# Sheet1.net
KiCad netlist of a schematic drawn in Altium Designer
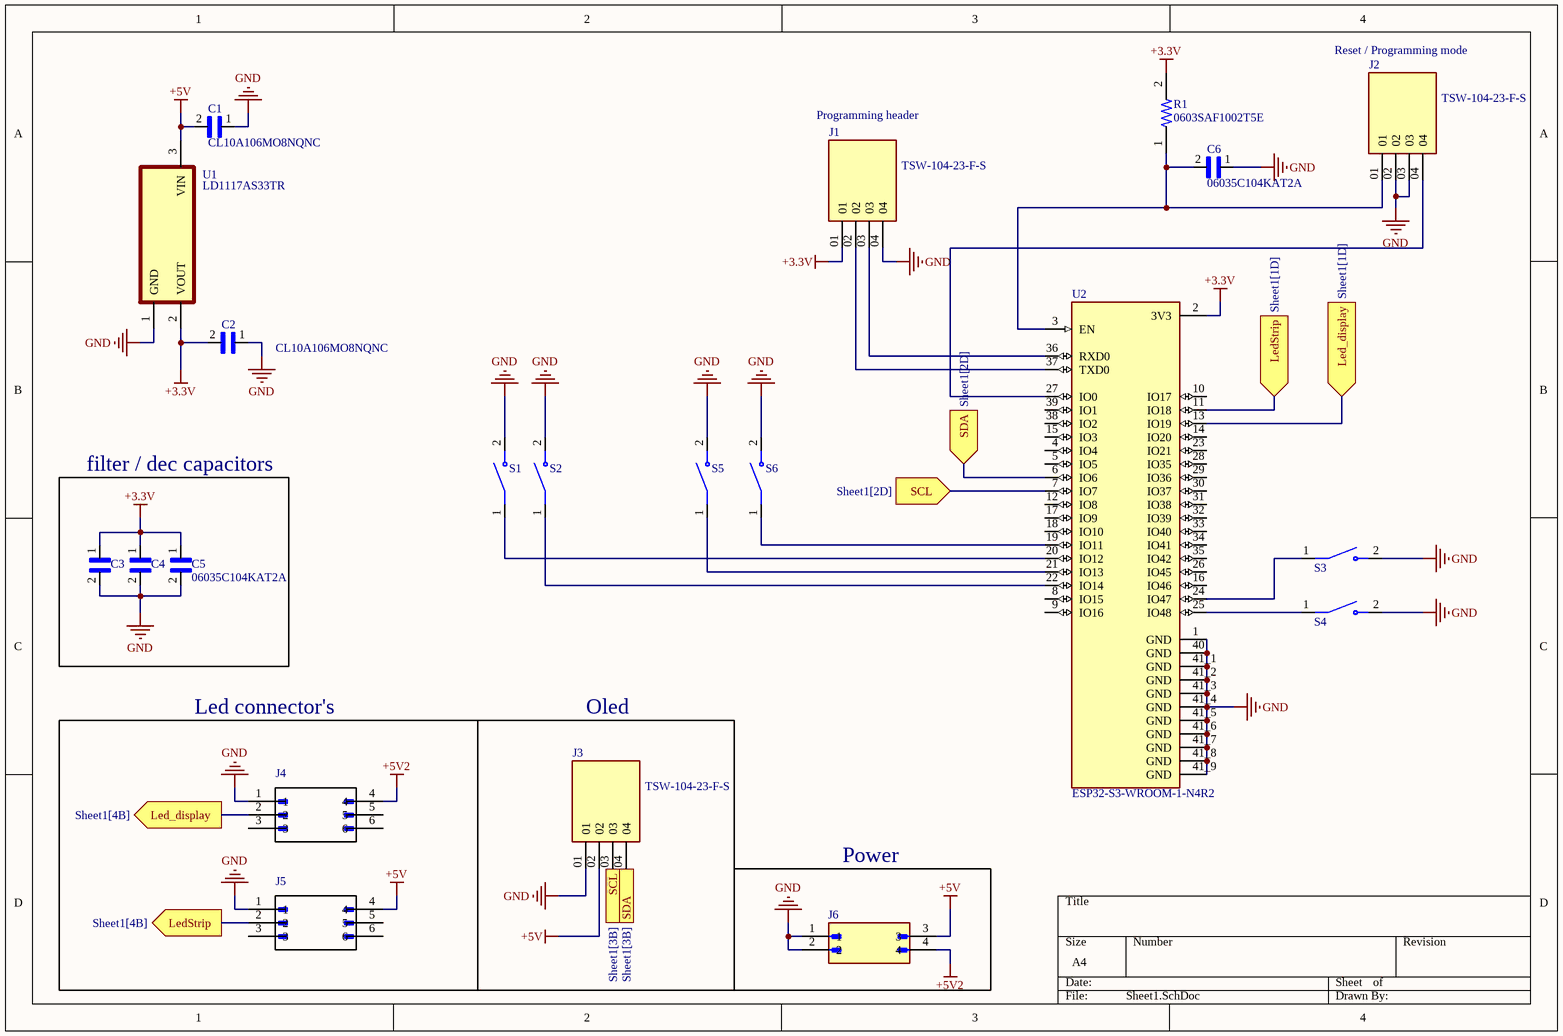
[diagram p0: Sheet1.SchDoc]

(export (version "E")
  (design (tool "Eeschema 10.0.6"))
  (components
    (comp (ref "C1")
      (value "CL10A106MO8NQNC")
      (footprint "CL10A106MO8NQNC:CAPC1608X90N")
      (description "Cap Ceramic 10uF 16V X5R 20% SMD 0603 85Â°C Paper T/R")
      (fields (field (name "MF") "{'manufacturer': u'Samsung Electro-Mechanics'}"))
      (libsource (lib "*") (part "CL10A106MO8NQNC"))
    )
    (comp (ref "C2")
      (value "CL10A106MO8NQNC")
      (footprint "CL10A106MO8NQNC:CAPC1608X90N")
      (description "Cap Ceramic 10uF 16V X5R 20% SMD 0603 85Â°C Paper T/R")
      (fields (field (name "MF") "{'manufacturer': u'Samsung Electro-Mechanics'}"))
      (libsource (lib "*") (part "CL10A106MO8NQNC"))
    )
    (comp (ref "C3")
      (value "06035C104KAT2A")
      (footprint "06035C104KAT2A:CAPC1608X90N")
      (fields (field (name "MF") "{'manufacturer': u'AVX'}"))
      (libsource (lib "") (part "06035C104KAT2A_1"))
    )
    (comp (ref "C4")
      (value "06035C104KAT2A")
      (footprint "06035C104KAT2A:CAPC1608X90N")
      (fields (field (name "MF") "{'manufacturer': u'AVX'}"))
      (libsource (lib "") (part "06035C104KAT2A_1"))
    )
    (comp (ref "C5")
      (value "06035C104KAT2A")
      (footprint "06035C104KAT2A:CAPC1608X90N")
      (fields (field (name "MF") "{'manufacturer': u'AVX'}"))
      (libsource (lib "") (part "06035C104KAT2A_1"))
    )
    (comp (ref "C6")
      (value "06035C104KAT2A")
      (footprint "06035C104KAT2A:CAPC1608X90N")
      (fields (field (name "MF") "{'manufacturer': u'AVX'}"))
      (libsource (lib "*") (part "06035C104KAT2A"))
    )
    (comp (ref "J1")
      (value "TSW-104-23-F-S")
      (footprint "TSW-104-23-F-S:SAMTEC_TSW-104-23-F-S")
      (fields (field (name "MF") "{'manufacturer': u'Samtec'}"))
      (libsource (lib "*") (part "TSW-104-23-F-S"))
    )
    (comp (ref "J2")
      (value "TSW-104-23-F-S")
      (footprint "TSW-104-23-F-S:SAMTEC_TSW-104-23-F-S")
      (fields (field (name "MF") "{'manufacturer': u'Samtec'}"))
      (libsource (lib "*") (part "TSW-104-23-F-S"))
    )
    (comp (ref "J3")
      (value "TSW-104-23-F-S")
      (footprint "TSW-104-23-F-S:SAMTEC_TSW-104-23-F-S")
      (fields (field (name "MF") "{'manufacturer': u'Samtec'}"))
      (libsource (lib "*") (part "TSW-104-23-F-S"))
    )
    (comp (ref "J4")
      (value "874270602")
      (footprint "*MOLEX_874270602")
      (libsource (lib "874270602") (part "874270602"))
    )
    (comp (ref "J5")
      (value "874270602")
      (footprint "*MOLEX_874270602")
      (libsource (lib "874270602") (part "874270602"))
    )
    (comp (ref "J6")
      (value "353180420")
      (footprint "*MOLEX_353180420")
      (description "Connector Header Through Hole, Right Angle 4 position 0.165in (4.20mm)")
      (fields (field (name "MF") "{'manufacturer': u'Molex'}"))
      (libsource (lib "*") (part "353180420"))
    )
    (comp (ref "R1")
      (value "0603SAF1002T5E")
      (footprint "RP73PF1J10KBTDF:RESC1608X50N")
      (description "0603 10k ohm")
      (fields
        (field (name "MF") "{'manufacturer': u'TE Connectivity'}")
        (field (name "MP") "RP73PF1J10KBTDF")
      )
      (libsource (lib "*") (part "RP73PF1J10KBTDF"))
    )
    (comp (ref "S1")
      (value "TL1107BF130WQ")
      (footprint "SW_MX_reversible")
      (fields (field (name "MF") "{'manufacturer': u'E-Switch'}"))
      (libsource (lib "TL1107BF130WQ") (part "TL1107BF130WQ"))
    )
    (comp (ref "S2")
      (value "TL1107BF130WQ")
      (footprint "SW_MX_reversible")
      (fields (field (name "MF") "{'manufacturer': u'E-Switch'}"))
      (libsource (lib "TL1107BF130WQ") (part "TL1107BF130WQ"))
    )
    (comp (ref "S3")
      (value "TL1107BF130WQ")
      (footprint "SW_MX_reversible")
      (fields (field (name "MF") "{'manufacturer': u'E-Switch'}"))
      (libsource (lib "TL1107BF130WQ") (part "TL1107BF130WQ"))
    )
    (comp (ref "S4")
      (value "TL1107BF130WQ")
      (footprint "SW_MX_reversible")
      (fields (field (name "MF") "{'manufacturer': u'E-Switch'}"))
      (libsource (lib "TL1107BF130WQ") (part "TL1107BF130WQ"))
    )
    (comp (ref "S5")
      (value "TL1107BF130WQ")
      (footprint "SW_MX_reversible")
      (fields (field (name "MF") "{'manufacturer': u'E-Switch'}"))
      (libsource (lib "TL1107BF130WQ") (part "TL1107BF130WQ"))
    )
    (comp (ref "S6")
      (value "TL1107BF130WQ")
      (footprint "SW_MX_reversible")
      (fields (field (name "MF") "{'manufacturer': u'E-Switch'}"))
      (libsource (lib "TL1107BF130WQ") (part "TL1107BF130WQ"))
    )
    (comp (ref "U1")
      (value "LD1117AS33TR")
      (footprint "LD1117AS33TR:SOT230P700X180-4N")
      (fields (field (name "MF") "{'manufacturer': u'STMicroelectronics'}"))
      (libsource (lib "*") (part "LD1117AS33TR"))
    )
    (comp (ref "U2")
      (value "ESP32-S3-WROOM-1-N4R2")
      (footprint "XCVR_ESP32-S3-WROOM-1-N4R2")
      (fields (field (name "MF") "{'manufacturer': u'Espressif Systems'}"))
      (libsource (lib "ESP32-S3-WROOM-1-N4R2") (part "ESP32-S3-WROOM-1-N4R2"))
    )
  )
  (nets
    (net (code "1") (name "+3.3V") (class "Default")
      (node (ref "C2") (pin "2") (pinfunction "2_2") (pintype "passive"))
      (node (ref "C3") (pin "1") (pinfunction "1_1") (pintype "passive"))
      (node (ref "C4") (pin "1") (pinfunction "1_1") (pintype "passive"))
      (node (ref "C5") (pin "1") (pinfunction "1_1") (pintype "passive"))
      (node (ref "J1") (pin "01") (pinfunction "01_01") (pintype "passive"))
      (node (ref "R1") (pin "2") (pinfunction "2_2") (pintype "passive"))
      (node (ref "U1") (pin "2") (pinfunction "VOUT_2") (pintype "power_in"))
      (node (ref "U2") (pin "2") (pinfunction "3V3_2") (pintype "power_in"))
    )
    (net (code "2") (name "+5V") (class "Default")
      (node (ref "C1") (pin "2") (pinfunction "2_2") (pintype "passive"))
      (node (ref "J3") (pin "02") (pinfunction "02_02") (pintype "passive"))
      (node (ref "J5") (pin "4") (pinfunction "4_4") (pintype "passive"))
      (node (ref "J6") (pin "3") (pinfunction "3_3") (pintype "passive"))
      (node (ref "U1") (pin "3") (pinfunction "VIN_3") (pintype "power_in"))
    )
    (net (code "3") (name "+5V2") (class "Default")
      (node (ref "J4") (pin "4") (pinfunction "4_4") (pintype "passive"))
      (node (ref "J6") (pin "4") (pinfunction "4_4") (pintype "passive"))
    )
    (net (code "4") (name "/LedStrip") (class "Default")
      (node (ref "J5") (pin "2") (pinfunction "2_2") (pintype "passive"))
      (node (ref "U2") (pin "11") (pinfunction "IO18_11") (pintype "bidirectional"))
    )
    (net (code "5") (name "/Led_display") (class "Default")
      (node (ref "J4") (pin "2") (pinfunction "2_2") (pintype "passive"))
      (node (ref "U2") (pin "13") (pinfunction "IO19_13") (pintype "bidirectional"))
    )
    (net (code "6") (name "/SCL") (class "Default")
      (node (ref "J3") (pin "03") (pinfunction "03_03") (pintype "passive"))
      (node (ref "U2") (pin "7") (pinfunction "IO7_7") (pintype "bidirectional"))
    )
    (net (code "7") (name "/SDA") (class "Default")
      (node (ref "J3") (pin "04") (pinfunction "04_04") (pintype "passive"))
      (node (ref "U2") (pin "6") (pinfunction "IO6_6") (pintype "bidirectional"))
    )
    (net (code "8") (name "GND") (class "Default")
      (node (ref "C1") (pin "1") (pinfunction "1_1") (pintype "passive"))
      (node (ref "C2") (pin "1") (pinfunction "1_1") (pintype "passive"))
      (node (ref "C3") (pin "2") (pinfunction "2_2") (pintype "passive"))
      (node (ref "C4") (pin "2") (pinfunction "2_2") (pintype "passive"))
      (node (ref "C5") (pin "2") (pinfunction "2_2") (pintype "passive"))
      (node (ref "C6") (pin "1") (pinfunction "1_1") (pintype "power_in"))
      (node (ref "J1") (pin "04") (pinfunction "04_04") (pintype "passive"))
      (node (ref "J2") (pin "02") (pinfunction "02_02") (pintype "passive"))
      (node (ref "J2") (pin "03") (pinfunction "03_03") (pintype "passive"))
      (node (ref "J3") (pin "01") (pinfunction "01_01") (pintype "passive"))
      (node (ref "J4") (pin "1") (pinfunction "1_1") (pintype "passive"))
      (node (ref "J5") (pin "1") (pinfunction "1_1") (pintype "passive"))
      (node (ref "J6") (pin "1") (pinfunction "1_1") (pintype "passive"))
      (node (ref "J6") (pin "2") (pinfunction "2_2") (pintype "passive"))
      (node (ref "S1") (pin "2") (pinfunction "2_2") (pintype "passive"))
      (node (ref "S2") (pin "2") (pinfunction "2_2") (pintype "passive"))
      (node (ref "S3") (pin "2") (pinfunction "2_2") (pintype "passive"))
      (node (ref "S4") (pin "2") (pinfunction "2_2") (pintype "passive"))
      (node (ref "S5") (pin "2") (pinfunction "2_2") (pintype "passive"))
      (node (ref "S6") (pin "2") (pinfunction "2_2") (pintype "passive"))
      (node (ref "U1") (pin "1") (pinfunction "GND_1") (pintype "power_in"))
      (node (ref "U2") (pin "1") (pinfunction "GND_1") (pintype "power_in"))
      (node (ref "U2") (pin "40") (pinfunction "GND_40") (pintype "power_in"))
      (node (ref "U2") (pin "41_1") (pinfunction "GND_41_1") (pintype "power_in"))
      (node (ref "U2") (pin "41_2") (pinfunction "GND_41_2") (pintype "power_in"))
      (node (ref "U2") (pin "41_3") (pinfunction "GND_41_3") (pintype "power_in"))
      (node (ref "U2") (pin "41_4") (pinfunction "GND_41_4") (pintype "power_in"))
      (node (ref "U2") (pin "41_5") (pinfunction "GND_41_5") (pintype "power_in"))
      (node (ref "U2") (pin "41_6") (pinfunction "GND_41_6") (pintype "power_in"))
      (node (ref "U2") (pin "41_7") (pinfunction "GND_41_7") (pintype "power_in"))
      (node (ref "U2") (pin "41_8") (pinfunction "GND_41_8") (pintype "power_in"))
      (node (ref "U2") (pin "41_9") (pinfunction "GND_41_9") (pintype "power_in"))
    )
    (net (code "9") (name "Net-(U2-EN)") (class "Default")
      (node (ref "C6") (pin "2") (pinfunction "2_2") (pintype "power_in"))
      (node (ref "J2") (pin "01") (pinfunction "01_01") (pintype "passive"))
      (node (ref "R1") (pin "1") (pinfunction "1_1") (pintype "passive"))
      (node (ref "U2") (pin "3") (pinfunction "EN_3") (pintype "input"))
    )
    (net (code "10") (name "Net-(U2-IO0)") (class "Default")
      (node (ref "J2") (pin "04") (pinfunction "04_04") (pintype "passive"))
      (node (ref "U2") (pin "27") (pinfunction "IO0_27") (pintype "bidirectional"))
    )
    (net (code "11") (name "Net-(U2-IO11)") (class "Default")
      (node (ref "S6") (pin "1") (pinfunction "1_1") (pintype "passive"))
      (node (ref "U2") (pin "19") (pinfunction "IO11_19") (pintype "bidirectional"))
    )
    (net (code "12") (name "Net-(U2-IO12)") (class "Default")
      (node (ref "S1") (pin "1") (pinfunction "1_1") (pintype "passive"))
      (node (ref "U2") (pin "20") (pinfunction "IO12_20") (pintype "bidirectional"))
    )
    (net (code "13") (name "Net-(U2-IO13)") (class "Default")
      (node (ref "S5") (pin "1") (pinfunction "1_1") (pintype "passive"))
      (node (ref "U2") (pin "21") (pinfunction "IO13_21") (pintype "bidirectional"))
    )
    (net (code "14") (name "Net-(U2-IO14)") (class "Default")
      (node (ref "S2") (pin "1") (pinfunction "1_1") (pintype "passive"))
      (node (ref "U2") (pin "22") (pinfunction "IO14_22") (pintype "bidirectional"))
    )
    (net (code "15") (name "Net-(U2-IO47)") (class "Default")
      (node (ref "S3") (pin "1") (pinfunction "1_1") (pintype "passive"))
      (node (ref "U2") (pin "24") (pinfunction "IO47_24") (pintype "bidirectional"))
    )
    (net (code "16") (name "Net-(U2-IO48)") (class "Default")
      (node (ref "S4") (pin "1") (pinfunction "1_1") (pintype "passive"))
      (node (ref "U2") (pin "25") (pinfunction "IO48_25") (pintype "bidirectional"))
    )
    (net (code "17") (name "Net-(U2-RXD0)") (class "Default")
      (node (ref "J1") (pin "03") (pinfunction "03_03") (pintype "passive"))
      (node (ref "U2") (pin "36") (pinfunction "RXD0_36") (pintype "bidirectional"))
    )
    (net (code "18") (name "Net-(U2-TXD0)") (class "Default")
      (node (ref "J1") (pin "02") (pinfunction "02_02") (pintype "passive"))
      (node (ref "U2") (pin "37") (pinfunction "TXD0_37") (pintype "bidirectional"))
    )
    (net (code "19") (name "unconnected-(J4-Pad3)") (class "Default")
      (node (ref "J4") (pin "3") (pinfunction "3_3") (pintype "passive"))
    )
    (net (code "20") (name "unconnected-(J4-Pad5)") (class "Default")
      (node (ref "J4") (pin "5") (pinfunction "5_5") (pintype "passive"))
    )
    (net (code "21") (name "unconnected-(J4-Pad6)") (class "Default")
      (node (ref "J4") (pin "6") (pinfunction "6_6") (pintype "passive"))
    )
    (net (code "22") (name "unconnected-(J5-Pad3)") (class "Default")
      (node (ref "J5") (pin "3") (pinfunction "3_3") (pintype "passive"))
    )
    (net (code "23") (name "unconnected-(J5-Pad5)") (class "Default")
      (node (ref "J5") (pin "5") (pinfunction "5_5") (pintype "passive"))
    )
    (net (code "24") (name "unconnected-(J5-Pad6)") (class "Default")
      (node (ref "J5") (pin "6") (pinfunction "6_6") (pintype "passive"))
    )
    (net (code "25") (name "unconnected-(U2-IO1-Pad39)") (class "Default")
      (node (ref "U2") (pin "39") (pinfunction "IO1_39") (pintype "bidirectional"))
    )
    (net (code "26") (name "unconnected-(U2-IO2-Pad38)") (class "Default")
      (node (ref "U2") (pin "38") (pinfunction "IO2_38") (pintype "bidirectional"))
    )
    (net (code "27") (name "unconnected-(U2-IO3-Pad15)") (class "Default")
      (node (ref "U2") (pin "15") (pinfunction "IO3_15") (pintype "bidirectional"))
    )
    (net (code "28") (name "unconnected-(U2-IO4-Pad4)") (class "Default")
      (node (ref "U2") (pin "4") (pinfunction "IO4_4") (pintype "bidirectional"))
    )
    (net (code "29") (name "unconnected-(U2-IO5-Pad5)") (class "Default")
      (node (ref "U2") (pin "5") (pinfunction "IO5_5") (pintype "bidirectional"))
    )
    (net (code "30") (name "unconnected-(U2-IO8-Pad12)") (class "Default")
      (node (ref "U2") (pin "12") (pinfunction "IO8_12") (pintype "bidirectional"))
    )
    (net (code "31") (name "unconnected-(U2-IO9-Pad17)") (class "Default")
      (node (ref "U2") (pin "17") (pinfunction "IO9_17") (pintype "bidirectional"))
    )
    (net (code "32") (name "unconnected-(U2-IO10-Pad18)") (class "Default")
      (node (ref "U2") (pin "18") (pinfunction "IO10_18") (pintype "bidirectional"))
    )
    (net (code "33") (name "unconnected-(U2-IO15-Pad8)") (class "Default")
      (node (ref "U2") (pin "8") (pinfunction "IO15_8") (pintype "bidirectional"))
    )
    (net (code "34") (name "unconnected-(U2-IO16-Pad9)") (class "Default")
      (node (ref "U2") (pin "9") (pinfunction "IO16_9") (pintype "bidirectional"))
    )
    (net (code "35") (name "unconnected-(U2-IO17-Pad10)") (class "Default")
      (node (ref "U2") (pin "10") (pinfunction "IO17_10") (pintype "bidirectional"))
    )
    (net (code "36") (name "unconnected-(U2-IO20-Pad14)") (class "Default")
      (node (ref "U2") (pin "14") (pinfunction "IO20_14") (pintype "bidirectional"))
    )
    (net (code "37") (name "unconnected-(U2-IO21-Pad23)") (class "Default")
      (node (ref "U2") (pin "23") (pinfunction "IO21_23") (pintype "bidirectional"))
    )
    (net (code "38") (name "unconnected-(U2-IO35-Pad28)") (class "Default")
      (node (ref "U2") (pin "28") (pinfunction "IO35_28") (pintype "bidirectional"))
    )
    (net (code "39") (name "unconnected-(U2-IO36-Pad29)") (class "Default")
      (node (ref "U2") (pin "29") (pinfunction "IO36_29") (pintype "bidirectional"))
    )
    (net (code "40") (name "unconnected-(U2-IO37-Pad30)") (class "Default")
      (node (ref "U2") (pin "30") (pinfunction "IO37_30") (pintype "bidirectional"))
    )
    (net (code "41") (name "unconnected-(U2-IO38-Pad31)") (class "Default")
      (node (ref "U2") (pin "31") (pinfunction "IO38_31") (pintype "bidirectional"))
    )
    (net (code "42") (name "unconnected-(U2-IO39-Pad32)") (class "Default")
      (node (ref "U2") (pin "32") (pinfunction "IO39_32") (pintype "bidirectional"))
    )
    (net (code "43") (name "unconnected-(U2-IO40-Pad33)") (class "Default")
      (node (ref "U2") (pin "33") (pinfunction "IO40_33") (pintype "bidirectional"))
    )
    (net (code "44") (name "unconnected-(U2-IO41-Pad34)") (class "Default")
      (node (ref "U2") (pin "34") (pinfunction "IO41_34") (pintype "bidirectional"))
    )
    (net (code "45") (name "unconnected-(U2-IO42-Pad35)") (class "Default")
      (node (ref "U2") (pin "35") (pinfunction "IO42_35") (pintype "bidirectional"))
    )
    (net (code "46") (name "unconnected-(U2-IO45-Pad26)") (class "Default")
      (node (ref "U2") (pin "26") (pinfunction "IO45_26") (pintype "bidirectional"))
    )
    (net (code "47") (name "unconnected-(U2-IO46-Pad16)") (class "Default")
      (node (ref "U2") (pin "16") (pinfunction "IO46_16") (pintype "bidirectional"))
    )
  )
)
